# 9_Microphone_Input.net
KiCad netlist of a schematic drawn in Altium Designer
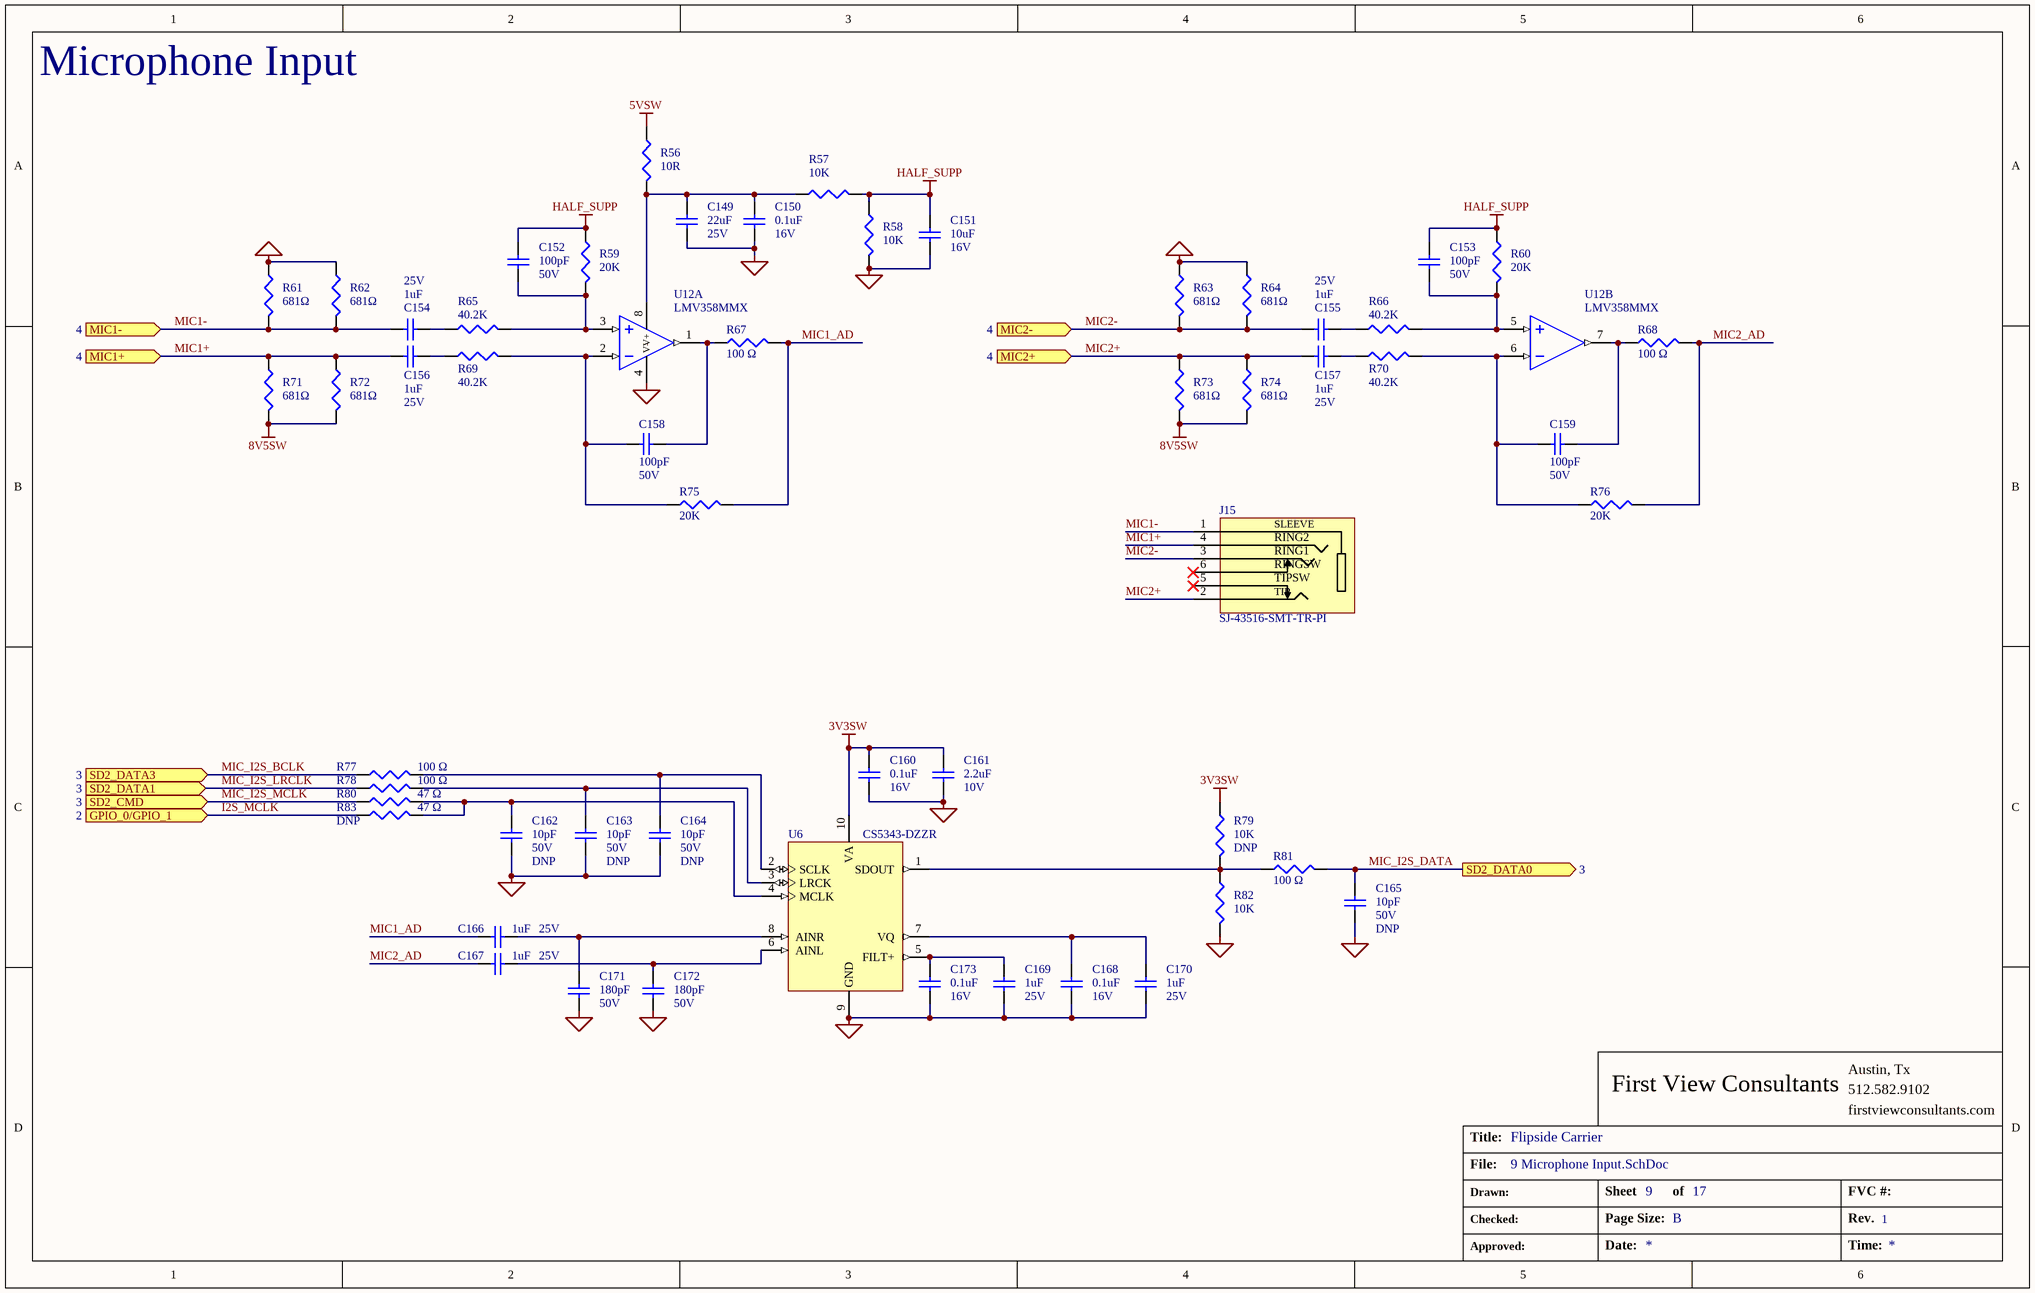
[diagram p0: 9 Microphone Input.SchDoc]

(export (version "E")
  (design (tool "Eeschema 10.0.6"))
  (components
    (comp (ref "C149")
      (value "22uF")
      (footprint "CAP_0805")
      (description "Cap, Cer, 22uF, 25V, 20%, X5R, 0805")
      (fields
        (field (name "TOLERANCE") "±20%")
        (field (name "MANUFACTURER") "Samsung Electro-Mechanics America, Inc")
        (field (name "VOLTAGE") "25V")
      )
      (libsource (lib "Firstview") (part "Cap 22uF 25V 0805"))
    )
    (comp (ref "C150")
      (value "0.1uF")
      (footprint "CAP_0402")
      (description "Cap, Cer, 0.1uF, 16V, 10%, X7R, 0402")
      (fields
        (field (name "TOLERANCE") "±10%")
        (field (name "MANUFACTURER") "Murata Electronics North America")
        (field (name "VOLTAGE") "16V")
      )
      (libsource (lib "Firstview") (part "Cap 0.1uF 16V 0402"))
    )
    (comp (ref "C151")
      (value "10uF")
      (footprint "CAP_0603")
      (description "Cap, Cer, 10uF, 16V, 20%, X5R, 0603")
      (fields
        (field (name "TOLERANCE") "±20%")
        (field (name "MANUFACTURER") "Murata Electronics North America")
        (field (name "VOLTAGE") "16V")
      )
      (libsource (lib "Firstview") (part "Cap 10uF 16V 0603"))
    )
    (comp (ref "C152")
      (value "100pF")
      (footprint "CAP_0402")
      (description "Cap, Cer, 100pF, 50V, 5%, C0G/NP0, 0402")
      (fields
        (field (name "TOLERANCE") "5%")
        (field (name "MANUFACTURER") "Yageo")
        (field (name "VOLTAGE") "50V")
      )
      (libsource (lib "Firstview") (part "Cap 100pF 50V 0402"))
    )
    (comp (ref "C153")
      (value "100pF")
      (footprint "CAP_0402")
      (description "Cap, Cer, 100pF, 50V, 5%, C0G/NP0, 0402")
      (fields
        (field (name "TOLERANCE") "5%")
        (field (name "MANUFACTURER") "Yageo")
        (field (name "VOLTAGE") "50V")
      )
      (libsource (lib "Firstview") (part "Cap 100pF 50V 0402"))
    )
    (comp (ref "C154")
      (value "1uF")
      (footprint "CAP_0402")
      (description "Cap, Cer, 1uF, 25V, 10%, X5R, 0402")
      (fields
        (field (name "MANUFACTURER") "Taiyo Yuden")
        (field (name "VOLTAGE") "25V")
        (field (name "Comment") "Cap 1uF 25V 0402")
      )
      (libsource (lib "Firstview") (part "Cap 1uF 25V 0402"))
    )
    (comp (ref "C155")
      (value "1uF")
      (footprint "CAP_0402")
      (description "Cap, Cer, 1uF, 25V, 10%, X5R, 0402")
      (fields
        (field (name "MANUFACTURER") "Taiyo Yuden")
        (field (name "VOLTAGE") "25V")
        (field (name "Comment") "Cap 1uF 25V 0402")
      )
      (libsource (lib "Firstview") (part "Cap 1uF 25V 0402"))
    )
    (comp (ref "C156")
      (value "1uF")
      (footprint "CAP_0402")
      (description "Cap, Cer, 1uF, 25V, 10%, X5R, 0402")
      (fields
        (field (name "MANUFACTURER") "Taiyo Yuden")
        (field (name "VOLTAGE") "25V")
        (field (name "Comment") "Cap 1uF 25V 0402")
      )
      (libsource (lib "Firstview") (part "Cap 1uF 25V 0402"))
    )
    (comp (ref "C157")
      (value "1uF")
      (footprint "CAP_0402")
      (description "Cap, Cer, 1uF, 25V, 10%, X5R, 0402")
      (fields
        (field (name "MANUFACTURER") "Taiyo Yuden")
        (field (name "VOLTAGE") "25V")
        (field (name "Comment") "Cap 1uF 25V 0402")
      )
      (libsource (lib "Firstview") (part "Cap 1uF 25V 0402"))
    )
    (comp (ref "C158")
      (value "100pF")
      (footprint "CAP_0402")
      (description "Cap, Cer, 100pF, 50V, 5%, C0G/NP0, 0402")
      (fields
        (field (name "TOLERANCE") "5%")
        (field (name "MANUFACTURER") "Yageo")
        (field (name "VOLTAGE") "50V")
      )
      (libsource (lib "Firstview") (part "Cap 100pF 50V 0402"))
    )
    (comp (ref "C159")
      (value "100pF")
      (footprint "CAP_0402")
      (description "Cap, Cer, 100pF, 50V, 5%, C0G/NP0, 0402")
      (fields
        (field (name "TOLERANCE") "5%")
        (field (name "MANUFACTURER") "Yageo")
        (field (name "VOLTAGE") "50V")
      )
      (libsource (lib "Firstview") (part "Cap 100pF 50V 0402"))
    )
    (comp (ref "C160")
      (value "0.1uF")
      (footprint "CAP_0402")
      (description "Cap, Cer, 0.1uF, 16V, 10%, X7R, 0402")
      (fields
        (field (name "TOLERANCE") "±10%")
        (field (name "MANUFACTURER") "Murata Electronics North America")
        (field (name "VOLTAGE") "16V")
      )
      (libsource (lib "Firstview") (part "Cap 0.1uF 16V 0402"))
    )
    (comp (ref "C161")
      (value "2.2uF")
      (footprint "CAP_0402")
      (description "Cap, Cer, 2.2uF, 10V, 10%, X5R, 0402")
      (fields
        (field (name "VOLTAGE") "10V")
        (field (name "MANUFACTURER") "Kemet")
        (field (name "Comment") "Cap 2.2uF 10V 0402")
      )
      (libsource (lib "Firstview") (part "Cap 2.2uF 10V 0402"))
    )
    (comp (ref "C162")
      (value "10pF")
      (footprint "CAP_0402")
      (description "Cap, Cer, 10pF, 50V, 5%, C0G/NP0, 0402")
      (fields
        (field (name "DNP") "DNP")
        (field (name "TOLERANCE") "5%")
        (field (name "MANUFACTURER") "Yageo")
        (field (name "VOLTAGE") "50V")
      )
      (libsource (lib "Firstview") (part "Cap 10pF 50V 0402"))
    )
    (comp (ref "C163")
      (value "10pF")
      (footprint "CAP_0402")
      (description "Cap, Cer, 10pF, 50V, 5%, C0G/NP0, 0402")
      (fields
        (field (name "DNP") "DNP")
        (field (name "TOLERANCE") "5%")
        (field (name "MANUFACTURER") "Yageo")
        (field (name "VOLTAGE") "50V")
      )
      (libsource (lib "Firstview") (part "Cap 10pF 50V 0402"))
    )
    (comp (ref "C164")
      (value "10pF")
      (footprint "CAP_0402")
      (description "Cap, Cer, 10pF, 50V, 5%, C0G/NP0, 0402")
      (fields
        (field (name "DNP") "DNP")
        (field (name "TOLERANCE") "5%")
        (field (name "MANUFACTURER") "Yageo")
        (field (name "VOLTAGE") "50V")
      )
      (libsource (lib "Firstview") (part "Cap 10pF 50V 0402"))
    )
    (comp (ref "C165")
      (value "10pF")
      (footprint "CAP_0402")
      (description "Cap, Cer, 10pF, 50V, 5%, C0G/NP0, 0402")
      (fields
        (field (name "DNP") "DNP")
        (field (name "TOLERANCE") "5%")
        (field (name "MANUFACTURER") "Yageo")
        (field (name "VOLTAGE") "50V")
      )
      (libsource (lib "Firstview") (part "Cap 10pF 50V 0402"))
    )
    (comp (ref "C166")
      (value "1uF")
      (footprint "CAP_0402")
      (description "Cap, Cer, 1uF, 25V, 10%, X5R, 0402")
      (fields
        (field (name "MANUFACTURER") "Taiyo Yuden")
        (field (name "VOLTAGE") "25V")
        (field (name "Comment") "Cap 1uF 25V 0402")
      )
      (libsource (lib "Firstview") (part "Cap 1uF 25V 0402"))
    )
    (comp (ref "C167")
      (value "1uF")
      (footprint "CAP_0402")
      (description "Cap, Cer, 1uF, 25V, 10%, X5R, 0402")
      (fields
        (field (name "MANUFACTURER") "Taiyo Yuden")
        (field (name "VOLTAGE") "25V")
        (field (name "Comment") "Cap 1uF 25V 0402")
      )
      (libsource (lib "Firstview") (part "Cap 1uF 25V 0402"))
    )
    (comp (ref "C168")
      (value "0.1uF")
      (footprint "CAP_0402")
      (description "Cap, Cer, 0.1uF, 16V, 10%, X7R, 0402")
      (fields
        (field (name "TOLERANCE") "±10%")
        (field (name "MANUFACTURER") "Murata Electronics North America")
        (field (name "VOLTAGE") "16V")
      )
      (libsource (lib "Firstview") (part "Cap 0.1uF 16V 0402"))
    )
    (comp (ref "C169")
      (value "1uF")
      (footprint "CAP_0402")
      (description "Cap, Cer, 1uF, 25V, 10%, X5R, 0402")
      (fields
        (field (name "MANUFACTURER") "Taiyo Yuden")
        (field (name "VOLTAGE") "25V")
        (field (name "Comment") "Cap 1uF 25V 0402")
      )
      (libsource (lib "Firstview") (part "Cap 1uF 25V 0402"))
    )
    (comp (ref "C170")
      (value "1uF")
      (footprint "CAP_0402")
      (description "Cap, Cer, 1uF, 25V, 10%, X5R, 0402")
      (fields
        (field (name "MANUFACTURER") "Taiyo Yuden")
        (field (name "VOLTAGE") "25V")
        (field (name "Comment") "Cap 1uF 25V 0402")
      )
      (libsource (lib "Firstview") (part "Cap 1uF 25V 0402"))
    )
    (comp (ref "C171")
      (value "180pF")
      (footprint "CAP_0402")
      (description "Cap, Cer, 180pF, 50V, 5%, NP0, 0402")
      (fields
        (field (name "TOLERANCE") "5%")
        (field (name "MANUFACTURER") "Murata Electronics North America")
        (field (name "VOLTAGE") "50V")
      )
      (libsource (lib "Firstview") (part "Cap 180pF 50V 0402"))
    )
    (comp (ref "C172")
      (value "180pF")
      (footprint "CAP_0402")
      (description "Cap, Cer, 180pF, 50V, 5%, NP0, 0402")
      (fields
        (field (name "TOLERANCE") "5%")
        (field (name "MANUFACTURER") "Murata Electronics North America")
        (field (name "VOLTAGE") "50V")
      )
      (libsource (lib "Firstview") (part "Cap 180pF 50V 0402"))
    )
    (comp (ref "C173")
      (value "0.1uF")
      (footprint "CAP_0402")
      (description "Cap, Cer, 0.1uF, 16V, 10%, X7R, 0402")
      (fields
        (field (name "TOLERANCE") "±10%")
        (field (name "MANUFACTURER") "Murata Electronics North America")
        (field (name "VOLTAGE") "16V")
      )
      (libsource (lib "Firstview") (part "Cap 0.1uF 16V 0402"))
    )
    (comp (ref "J15")
      (value "SJ-43516-SMT-TR-PI")
      (footprint "CON_SJ-43516-SMT")
      (description "Conn, Audio Jack, 3.5mm, Pink, SMD")
      (fields (field (name "MANUFACTURER") "CUI Inc"))
      (libsource (lib "Firstview") (part "SJ-43516-SMT-TR-PI"))
    )
    (comp (ref "R56")
      (value "10R")
      (footprint "RES_0402")
      (description "Res, 10R, 0.1W, 0402")
      (fields
        (field (name "MANUFACTURER") "Panasonic Electronic Components")
        (field (name "Comment") "Res 10R 0.1W")
      )
      (libsource (lib "Firstview") (part "Res 10R 0.1W"))
    )
    (comp (ref "R57")
      (value "10K")
      (footprint "RES_0402")
      (description "Res, 10K, 1/16W, 1%, 0402")
      (fields (field (name "MANUFACTURER") "Yageo") (field (name "Comment") "Res 10K 0.063W"))
      (libsource (lib "Firstview") (part "Res 10K 0.063W"))
    )
    (comp (ref "R58")
      (value "10K")
      (footprint "RES_0402")
      (description "Res, 10K, 1/16W, 1%, 0402")
      (fields (field (name "MANUFACTURER") "Yageo") (field (name "Comment") "Res 10K 0.063W"))
      (libsource (lib "Firstview") (part "Res 10K 0.063W"))
    )
    (comp (ref "R59")
      (value "20K")
      (footprint "RES_0402")
      (description "Res, 20K, 0.1W, 1%, 0402")
      (fields
        (field (name "MANUFACTURER") "Panasonic Electronic Components")
        (field (name "Comment") "Res 20K 0.1W")
      )
      (libsource (lib "Firstview") (part "Res 20K 0.1W"))
    )
    (comp (ref "R60")
      (value "20K")
      (footprint "RES_0402")
      (description "Res, 20K, 0.1W, 1%, 0402")
      (fields
        (field (name "MANUFACTURER") "Panasonic Electronic Components")
        (field (name "Comment") "Res 20K 0.1W")
      )
      (libsource (lib "Firstview") (part "Res 20K 0.1W"))
    )
    (comp (ref "R61")
      (value "681Ω")
      (footprint "RES_1210")
      (description "Res, 681R, 0.5W, 1%, 1210")
      (fields (field (name "TOLERANCE") "1%") (field (name "MANUFACTURER") "Panasonic Electronic Components"))
      (libsource (lib "Firstview") (part "Res 681R 0.5W"))
    )
    (comp (ref "R62")
      (value "681Ω")
      (footprint "RES_1210")
      (description "Res, 681R, 0.5W, 1%, 1210")
      (fields (field (name "TOLERANCE") "1%") (field (name "MANUFACTURER") "Panasonic Electronic Components"))
      (libsource (lib "Firstview") (part "Res 681R 0.5W"))
    )
    (comp (ref "R63")
      (value "681Ω")
      (footprint "RES_1210")
      (description "Res, 681R, 0.5W, 1%, 1210")
      (fields (field (name "TOLERANCE") "1%") (field (name "MANUFACTURER") "Panasonic Electronic Components"))
      (libsource (lib "Firstview") (part "Res 681R 0.5W"))
    )
    (comp (ref "R64")
      (value "681Ω")
      (footprint "RES_1210")
      (description "Res, 681R, 0.5W, 1%, 1210")
      (fields (field (name "TOLERANCE") "1%") (field (name "MANUFACTURER") "Panasonic Electronic Components"))
      (libsource (lib "Firstview") (part "Res 681R 0.5W"))
    )
    (comp (ref "R65")
      (value "40.2K")
      (footprint "RES_0402")
      (description "Res, 40.2K, 0.1W, 1%, 0402")
      (fields
        (field (name "MANUFACTURER") "Panasonic Electronic Components")
        (field (name "Comment") "Res 40.2K 0.1W")
      )
      (libsource (lib "Firstview") (part "Res 40.2K 0.1W"))
    )
    (comp (ref "R66")
      (value "40.2K")
      (footprint "RES_0402")
      (description "Res, 40.2K, 0.1W, 1%, 0402")
      (fields
        (field (name "MANUFACTURER") "Panasonic Electronic Components")
        (field (name "Comment") "Res 40.2K 0.1W")
      )
      (libsource (lib "Firstview") (part "Res 40.2K 0.1W"))
    )
    (comp (ref "R67")
      (value "100 Ω")
      (footprint "RES_0402")
      (description "Res, 100R, 0.063W, 1%, 0402")
      (fields
        (field (name "MANUFACTURER") "Murata Electronics North America")
        (field (name "Comment") "Res 100R 0.063W")
      )
      (libsource (lib "Firstview") (part "Res 100R 0.063W"))
    )
    (comp (ref "R68")
      (value "100 Ω")
      (footprint "RES_0402")
      (description "Res, 100R, 0.063W, 1%, 0402")
      (fields
        (field (name "MANUFACTURER") "Murata Electronics North America")
        (field (name "Comment") "Res 100R 0.063W")
      )
      (libsource (lib "Firstview") (part "Res 100R 0.063W"))
    )
    (comp (ref "R69")
      (value "40.2K")
      (footprint "RES_0402")
      (description "Res, 40.2K, 0.1W, 1%, 0402")
      (fields
        (field (name "MANUFACTURER") "Panasonic Electronic Components")
        (field (name "Comment") "Res 40.2K 0.1W")
      )
      (libsource (lib "Firstview") (part "Res 40.2K 0.1W"))
    )
    (comp (ref "R70")
      (value "40.2K")
      (footprint "RES_0402")
      (description "Res, 40.2K, 0.1W, 1%, 0402")
      (fields
        (field (name "MANUFACTURER") "Panasonic Electronic Components")
        (field (name "Comment") "Res 40.2K 0.1W")
      )
      (libsource (lib "Firstview") (part "Res 40.2K 0.1W"))
    )
    (comp (ref "R71")
      (value "681Ω")
      (footprint "RES_1210")
      (description "Res, 681R, 0.5W, 1%, 1210")
      (fields (field (name "TOLERANCE") "1%") (field (name "MANUFACTURER") "Panasonic Electronic Components"))
      (libsource (lib "Firstview") (part "Res 681R 0.5W"))
    )
    (comp (ref "R72")
      (value "681Ω")
      (footprint "RES_1210")
      (description "Res, 681R, 0.5W, 1%, 1210")
      (fields (field (name "TOLERANCE") "1%") (field (name "MANUFACTURER") "Panasonic Electronic Components"))
      (libsource (lib "Firstview") (part "Res 681R 0.5W"))
    )
    (comp (ref "R73")
      (value "681Ω")
      (footprint "RES_1210")
      (description "Res, 681R, 0.5W, 1%, 1210")
      (fields (field (name "TOLERANCE") "1%") (field (name "MANUFACTURER") "Panasonic Electronic Components"))
      (libsource (lib "Firstview") (part "Res 681R 0.5W"))
    )
    (comp (ref "R74")
      (value "681Ω")
      (footprint "RES_1210")
      (description "Res, 681R, 0.5W, 1%, 1210")
      (fields (field (name "TOLERANCE") "1%") (field (name "MANUFACTURER") "Panasonic Electronic Components"))
      (libsource (lib "Firstview") (part "Res 681R 0.5W"))
    )
    (comp (ref "R75")
      (value "20K")
      (footprint "RES_0402")
      (description "Res, 20K, 0.1W, 1%, 0402")
      (fields
        (field (name "MANUFACTURER") "Panasonic Electronic Components")
        (field (name "Comment") "Res 20K 0.1W")
      )
      (libsource (lib "Firstview") (part "Res 20K 0.1W"))
    )
    (comp (ref "R76")
      (value "20K")
      (footprint "RES_0402")
      (description "Res, 20K, 0.1W, 1%, 0402")
      (fields
        (field (name "MANUFACTURER") "Panasonic Electronic Components")
        (field (name "Comment") "Res 20K 0.1W")
      )
      (libsource (lib "Firstview") (part "Res 20K 0.1W"))
    )
    (comp (ref "R77")
      (value "100 Ω")
      (footprint "RES_0402")
      (description "Res, 100R, 0.063W, 1%, 0402")
      (fields
        (field (name "MANUFACTURER") "Murata Electronics North America")
        (field (name "Comment") "Res 100R 0.063W")
      )
      (libsource (lib "Firstview") (part "Res 100R 0.063W"))
    )
    (comp (ref "R78")
      (value "100 Ω")
      (footprint "RES_0402")
      (description "Res, 100R, 0.063W, 1%, 0402")
      (fields
        (field (name "MANUFACTURER") "Murata Electronics North America")
        (field (name "Comment") "Res 100R 0.063W")
      )
      (libsource (lib "Firstview") (part "Res 100R 0.063W"))
    )
    (comp (ref "R79")
      (value "10K")
      (footprint "RES_0402")
      (description "Res, 10K, 1/16W, 1%, 0402")
      (fields
        (field (name "DNP") "DNP")
        (field (name "MANUFACTURER") "Yageo")
        (field (name "Comment") "Res 10K 0.063W")
      )
      (libsource (lib "Firstview") (part "Res 10K 0.063W"))
    )
    (comp (ref "R80")
      (value "47 Ω")
      (footprint "RES_0402")
      (description "Res, 47R, 0.063W, 5%, 0402")
      (fields (field (name "TOLERANCE") "5%") (field (name "MANUFACTURER") "Stackpole Electronics Inc"))
      (libsource (lib "Firstview") (part "Res 47R 0.063W"))
    )
    (comp (ref "R81")
      (value "100 Ω")
      (footprint "RES_0402")
      (description "Res, 100R, 0.063W, 1%, 0402")
      (fields
        (field (name "MANUFACTURER") "Murata Electronics North America")
        (field (name "Comment") "Res 100R 0.063W")
      )
      (libsource (lib "Firstview") (part "Res 100R 0.063W"))
    )
    (comp (ref "R82")
      (value "10K")
      (footprint "RES_0402")
      (description "Res, 10K, 1/16W, 1%, 0402")
      (fields (field (name "MANUFACTURER") "Yageo") (field (name "Comment") "Res 10K 0.063W"))
      (libsource (lib "Firstview") (part "Res 10K 0.063W"))
    )
    (comp (ref "R83")
      (value "47 Ω")
      (footprint "RES_0402")
      (description "Res, 47R, 0.063W, 5%, 0402")
      (fields
        (field (name "DNP") "DNP")
        (field (name "TOLERANCE") "5%")
        (field (name "MANUFACTURER") "Stackpole Electronics Inc")
      )
      (libsource (lib "Firstview") (part "Res 47R 0.063W"))
    )
    (comp (ref "U6")
      (value "CS5343-DZZR")
      (footprint "TSSOP-10_CS5343")
      (description "IC, ADC, I2S, 98dB, Audio, TSSOP-10")
      (fields (field (name "MANUFACTURER") "Cirrus Logic"))
      (libsource (lib "Firstview") (part "CS5343-DZZR"))
    )
    (comp (ref "U12")
      (value "LMV358MMX")
      (footprint "VSSOP-8_LMV358MMX")
      (description "IC, Dual Op Amp, 2.7-5V, VSSOP-8")
      (fields (field (name "MANUFACTURER") "Texas Instruments"))
      (libsource (lib "Firstview") (part "LMV358MMX"))
    )
  )
  (nets
    (net (code "1") (name "/I2S_MCLK") (class "Default")
      (node (ref "R83") (pin "1") (pinfunction "1_1") (pintype "passive"))
    )
    (net (code "2") (name "/MIC1+") (class "Default")
      (node (ref "C156") (pin "1") (pinfunction "1_1") (pintype "passive"))
      (node (ref "J15") (pin "4") (pinfunction "RING_2_4") (pintype "passive"))
      (node (ref "R71") (pin "1") (pinfunction "1_1") (pintype "passive"))
      (node (ref "R72") (pin "1") (pinfunction "1_1") (pintype "passive"))
    )
    (net (code "3") (name "/MIC1-") (class "Default")
      (node (ref "C154") (pin "1") (pinfunction "1_1") (pintype "passive"))
      (node (ref "J15") (pin "1") (pinfunction "SLEEVE_1") (pintype "passive"))
      (node (ref "R61") (pin "2") (pinfunction "2_2") (pintype "passive"))
      (node (ref "R62") (pin "2") (pinfunction "2_2") (pintype "passive"))
    )
    (net (code "4") (name "/MIC1_AD") (class "Default")
      (node (ref "C166") (pin "1") (pinfunction "1_1") (pintype "passive"))
      (node (ref "R67") (pin "2") (pinfunction "2_2") (pintype "passive"))
      (node (ref "R75") (pin "2") (pinfunction "2_2") (pintype "passive"))
    )
    (net (code "5") (name "/MIC2+") (class "Default")
      (node (ref "C157") (pin "1") (pinfunction "1_1") (pintype "passive"))
      (node (ref "J15") (pin "2") (pinfunction "TIP_2") (pintype "passive"))
      (node (ref "R73") (pin "1") (pinfunction "1_1") (pintype "passive"))
      (node (ref "R74") (pin "1") (pinfunction "1_1") (pintype "passive"))
    )
    (net (code "6") (name "/MIC2-") (class "Default")
      (node (ref "C155") (pin "1") (pinfunction "1_1") (pintype "passive"))
      (node (ref "J15") (pin "3") (pinfunction "RING_1_3") (pintype "passive"))
      (node (ref "R63") (pin "2") (pinfunction "2_2") (pintype "passive"))
      (node (ref "R64") (pin "2") (pinfunction "2_2") (pintype "passive"))
    )
    (net (code "7") (name "/MIC2_AD") (class "Default")
      (node (ref "C167") (pin "1") (pinfunction "1_1") (pintype "passive"))
      (node (ref "R68") (pin "2") (pinfunction "2_2") (pintype "passive"))
      (node (ref "R76") (pin "2") (pinfunction "2_2") (pintype "passive"))
    )
    (net (code "8") (name "/MIC_I2S_BCLK") (class "Default")
      (node (ref "R77") (pin "1") (pinfunction "1_1") (pintype "passive"))
    )
    (net (code "9") (name "/MIC_I2S_DATA") (class "Default")
      (node (ref "C165") (pin "1") (pinfunction "1_1") (pintype "passive"))
      (node (ref "R81") (pin "2") (pinfunction "2_2") (pintype "passive"))
    )
    (net (code "10") (name "/MIC_I2S_LRCLK") (class "Default")
      (node (ref "R78") (pin "1") (pinfunction "1_1") (pintype "passive"))
    )
    (net (code "11") (name "/MIC_I2S_MCLK") (class "Default")
      (node (ref "R80") (pin "1") (pinfunction "1_1") (pintype "passive"))
    )
    (net (code "12") (name "3V3SW") (class "Default")
      (node (ref "C160") (pin "1") (pinfunction "1_1") (pintype "passive"))
      (node (ref "C161") (pin "1") (pinfunction "1_1") (pintype "passive"))
      (node (ref "R79") (pin "1") (pinfunction "1_1") (pintype "passive"))
      (node (ref "U6") (pin "10") (pinfunction "VA_10") (pintype "power_in"))
    )
    (net (code "13") (name "5VSW") (class "Default")
      (node (ref "R56") (pin "1") (pinfunction "1_1") (pintype "passive"))
    )
    (net (code "14") (name "8V5SW") (class "Default")
      (node (ref "R71") (pin "2") (pinfunction "2_2") (pintype "passive"))
      (node (ref "R72") (pin "2") (pinfunction "2_2") (pintype "passive"))
      (node (ref "R73") (pin "2") (pinfunction "2_2") (pintype "passive"))
      (node (ref "R74") (pin "2") (pinfunction "2_2") (pintype "passive"))
    )
    (net (code "15") (name "GND") (class "Default")
      (node (ref "C149") (pin "2") (pinfunction "2_2") (pintype "passive"))
      (node (ref "C150") (pin "2") (pinfunction "2_2") (pintype "passive"))
      (node (ref "C151") (pin "2") (pinfunction "2_2") (pintype "passive"))
      (node (ref "C160") (pin "2") (pinfunction "2_2") (pintype "passive"))
      (node (ref "C161") (pin "2") (pinfunction "2_2") (pintype "passive"))
      (node (ref "C162") (pin "2") (pinfunction "2_2") (pintype "passive"))
      (node (ref "C163") (pin "2") (pinfunction "2_2") (pintype "passive"))
      (node (ref "C164") (pin "2") (pinfunction "2_2") (pintype "passive"))
      (node (ref "C165") (pin "2") (pinfunction "2_2") (pintype "passive"))
      (node (ref "C168") (pin "2") (pinfunction "2_2") (pintype "passive"))
      (node (ref "C169") (pin "2") (pinfunction "2_2") (pintype "passive"))
      (node (ref "C170") (pin "2") (pinfunction "2_2") (pintype "passive"))
      (node (ref "C171") (pin "2") (pinfunction "2_2") (pintype "passive"))
      (node (ref "C172") (pin "2") (pinfunction "2_2") (pintype "passive"))
      (node (ref "C173") (pin "2") (pinfunction "2_2") (pintype "passive"))
      (node (ref "R58") (pin "2") (pinfunction "2_2") (pintype "passive"))
      (node (ref "R61") (pin "1") (pinfunction "1_1") (pintype "passive"))
      (node (ref "R62") (pin "1") (pinfunction "1_1") (pintype "passive"))
      (node (ref "R63") (pin "1") (pinfunction "1_1") (pintype "passive"))
      (node (ref "R64") (pin "1") (pinfunction "1_1") (pintype "passive"))
      (node (ref "R82") (pin "2") (pinfunction "2_2") (pintype "passive"))
      (node (ref "U12") (pin "4") (pinfunction "V-_4") (pintype "power_in"))
      (node (ref "U6") (pin "9") (pinfunction "GND_9") (pintype "power_in"))
    )
    (net (code "16") (name "HALF_SUPP") (class "Default")
      (node (ref "C151") (pin "1") (pinfunction "1_1") (pintype "passive"))
      (node (ref "C152") (pin "1") (pinfunction "1_1") (pintype "passive"))
      (node (ref "C153") (pin "1") (pinfunction "1_1") (pintype "passive"))
      (node (ref "R57") (pin "2") (pinfunction "2_2") (pintype "passive"))
      (node (ref "R58") (pin "1") (pinfunction "1_1") (pintype "passive"))
      (node (ref "R59") (pin "1") (pinfunction "1_1") (pintype "passive"))
      (node (ref "R60") (pin "1") (pinfunction "1_1") (pintype "passive"))
    )
    (net (code "17") (name "Net-(C154-Pad2)") (class "Default")
      (node (ref "C154") (pin "2") (pinfunction "2_2") (pintype "passive"))
      (node (ref "R65") (pin "1") (pinfunction "1_1") (pintype "passive"))
    )
    (net (code "18") (name "Net-(C155-Pad2)") (class "Default")
      (node (ref "C155") (pin "2") (pinfunction "2_2") (pintype "passive"))
      (node (ref "R66") (pin "1") (pinfunction "1_1") (pintype "passive"))
    )
    (net (code "19") (name "Net-(C156-Pad2)") (class "Default")
      (node (ref "C156") (pin "2") (pinfunction "2_2") (pintype "passive"))
      (node (ref "R69") (pin "1") (pinfunction "1_1") (pintype "passive"))
    )
    (net (code "20") (name "Net-(C157-Pad2)") (class "Default")
      (node (ref "C157") (pin "2") (pinfunction "2_2") (pintype "passive"))
      (node (ref "R70") (pin "1") (pinfunction "1_1") (pintype "passive"))
    )
    (net (code "21") (name "Net-(U6-AINL)") (class "Default")
      (node (ref "C167") (pin "2") (pinfunction "2_2") (pintype "passive"))
      (node (ref "C172") (pin "1") (pinfunction "1_1") (pintype "passive"))
      (node (ref "U6") (pin "6") (pinfunction "AINL_6") (pintype "input"))
    )
    (net (code "22") (name "Net-(U6-AINR)") (class "Default")
      (node (ref "C166") (pin "2") (pinfunction "2_2") (pintype "passive"))
      (node (ref "C171") (pin "1") (pinfunction "1_1") (pintype "passive"))
      (node (ref "U6") (pin "8") (pinfunction "AINR_8") (pintype "input"))
    )
    (net (code "23") (name "Net-(U6-FILT+)") (class "Default")
      (node (ref "C169") (pin "1") (pinfunction "1_1") (pintype "passive"))
      (node (ref "C173") (pin "1") (pinfunction "1_1") (pintype "passive"))
      (node (ref "U6") (pin "5") (pinfunction "FILT+_5") (pintype "output"))
    )
    (net (code "24") (name "Net-(U6-LRCK)") (class "Default")
      (node (ref "C163") (pin "1") (pinfunction "1_1") (pintype "passive"))
      (node (ref "R78") (pin "2") (pinfunction "2_2") (pintype "passive"))
      (node (ref "U6") (pin "3") (pinfunction "LRCK_3") (pintype "bidirectional"))
    )
    (net (code "25") (name "Net-(U6-MCLK)") (class "Default")
      (node (ref "C162") (pin "1") (pinfunction "1_1") (pintype "passive"))
      (node (ref "R80") (pin "2") (pinfunction "2_2") (pintype "passive"))
      (node (ref "R83") (pin "2") (pinfunction "2_2") (pintype "passive"))
      (node (ref "U6") (pin "4") (pinfunction "MCLK_4") (pintype "input"))
    )
    (net (code "26") (name "Net-(U6-SCLK)") (class "Default")
      (node (ref "C164") (pin "1") (pinfunction "1_1") (pintype "passive"))
      (node (ref "R77") (pin "2") (pinfunction "2_2") (pintype "passive"))
      (node (ref "U6") (pin "2") (pinfunction "SCLK_2") (pintype "bidirectional"))
    )
    (net (code "27") (name "Net-(U6-SDOUT)") (class "Default")
      (node (ref "R79") (pin "2") (pinfunction "2_2") (pintype "passive"))
      (node (ref "R81") (pin "1") (pinfunction "1_1") (pintype "passive"))
      (node (ref "R82") (pin "1") (pinfunction "1_1") (pintype "passive"))
      (node (ref "U6") (pin "1") (pinfunction "SDOUT_1") (pintype "output"))
    )
    (net (code "28") (name "Net-(U6-VQ)") (class "Default")
      (node (ref "C168") (pin "1") (pinfunction "1_1") (pintype "passive"))
      (node (ref "C170") (pin "1") (pinfunction "1_1") (pintype "passive"))
      (node (ref "U6") (pin "7") (pinfunction "VQ_7") (pintype "output"))
    )
    (net (code "29") (name "Net-(U12A-INA+)") (class "Default")
      (node (ref "C152") (pin "2") (pinfunction "2_2") (pintype "passive"))
      (node (ref "R59") (pin "2") (pinfunction "2_2") (pintype "passive"))
      (node (ref "R65") (pin "2") (pinfunction "2_2") (pintype "passive"))
      (node (ref "U12") (pin "3") (pinfunction "INA+_3") (pintype "input"))
    )
    (net (code "30") (name "Net-(U12A-INA-)") (class "Default")
      (node (ref "C158") (pin "1") (pinfunction "1_1") (pintype "passive"))
      (node (ref "R69") (pin "2") (pinfunction "2_2") (pintype "passive"))
      (node (ref "R75") (pin "1") (pinfunction "1_1") (pintype "passive"))
      (node (ref "U12") (pin "2") (pinfunction "INA-_2") (pintype "input"))
    )
    (net (code "31") (name "Net-(U12A-OUTA)") (class "Default")
      (node (ref "C158") (pin "2") (pinfunction "2_2") (pintype "passive"))
      (node (ref "R67") (pin "1") (pinfunction "1_1") (pintype "passive"))
      (node (ref "U12") (pin "1") (pinfunction "OUTA_1") (pintype "output"))
    )
    (net (code "32") (name "Net-(U12A-V+)") (class "Default")
      (node (ref "C149") (pin "1") (pinfunction "1_1") (pintype "passive"))
      (node (ref "C150") (pin "1") (pinfunction "1_1") (pintype "passive"))
      (node (ref "R56") (pin "2") (pinfunction "2_2") (pintype "passive"))
      (node (ref "R57") (pin "1") (pinfunction "1_1") (pintype "passive"))
      (node (ref "U12") (pin "8") (pinfunction "V+_8") (pintype "power_in"))
    )
    (net (code "33") (name "Net-(U12B-INB+)") (class "Default")
      (node (ref "C153") (pin "2") (pinfunction "2_2") (pintype "passive"))
      (node (ref "R60") (pin "2") (pinfunction "2_2") (pintype "passive"))
      (node (ref "R66") (pin "2") (pinfunction "2_2") (pintype "passive"))
      (node (ref "U12") (pin "5") (pinfunction "INB+_5") (pintype "input"))
    )
    (net (code "34") (name "Net-(U12B-INB-)") (class "Default")
      (node (ref "C159") (pin "1") (pinfunction "1_1") (pintype "passive"))
      (node (ref "R70") (pin "2") (pinfunction "2_2") (pintype "passive"))
      (node (ref "R76") (pin "1") (pinfunction "1_1") (pintype "passive"))
      (node (ref "U12") (pin "6") (pinfunction "INB-_6") (pintype "input"))
    )
    (net (code "35") (name "Net-(U12B-OUTB)") (class "Default")
      (node (ref "C159") (pin "2") (pinfunction "2_2") (pintype "passive"))
      (node (ref "R68") (pin "1") (pinfunction "1_1") (pintype "passive"))
      (node (ref "U12") (pin "7") (pinfunction "OUTB_7") (pintype "output"))
    )
    (net (code "36") (name "unconnected-(J15-RING_SW-Pad6)") (class "Default")
      (node (ref "J15") (pin "6") (pinfunction "RING_SW_6") (pintype "power_in+no_connect"))
    )
    (net (code "37") (name "unconnected-(J15-TIP_SW-Pad5)") (class "Default")
      (node (ref "J15") (pin "5") (pinfunction "TIP_SW_5") (pintype "power_in+no_connect"))
    )
  )
)
